# MSP430F249.net
KiCad netlist of a schematic drawn in Altium Designer
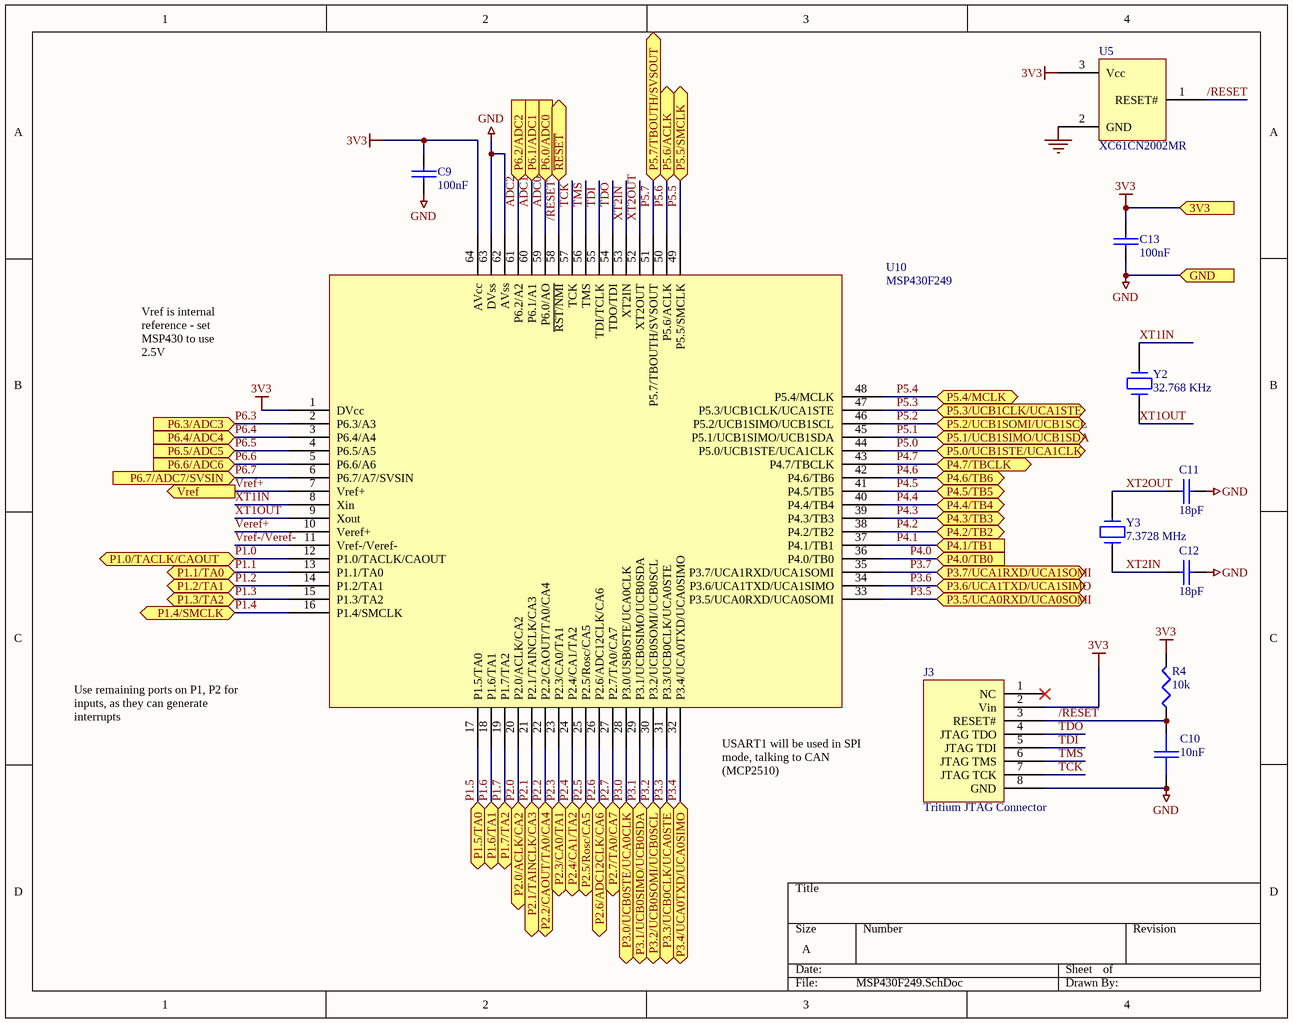
[diagram p0: MSP430F249.SchDoc]

(export (version "E")
  (design (tool "Eeschema 10.0.6"))
  (components
    (comp (ref "C9")
      (value "100nF")
      (footprint "0603")
      (description "Capacitor")
      (libsource (lib "*") (part "CAP"))
    )
    (comp (ref "C10")
      (value "10nF")
      (footprint "0603")
      (description "Capacitor")
      (libsource (lib "SunswiftLib20030312RR") (part "CAP"))
    )
    (comp (ref "C11")
      (value "18pF")
      (footprint "0603")
      (description "Capacitor")
      (libsource (lib "*") (part "CAP"))
    )
    (comp (ref "C12")
      (value "18pF")
      (footprint "0603")
      (description "Capacitor")
      (libsource (lib "*") (part "CAP"))
    )
    (comp (ref "C13")
      (value "100nF")
      (footprint "0603")
      (description "Capacitor")
      (libsource (lib "*") (part "CAP"))
    )
    (comp (ref "J3")
      (value "Tritium JTAG Connector")
      (footprint "IDC8")
      (description "Tritium JTAG interface for MSP430")
      (libsource (lib "MSP430") (part "430F_JTAG_TRITIUM"))
    )
    (comp (ref "R4")
      (value "10k")
      (footprint "0603")
      (description "Resistor")
      (libsource (lib "SunswiftLib20030312RR") (part "RES1"))
    )
    (comp (ref "U5")
      (value "XC61CN2002MR")
      (footprint "SOT23-3")
      (description "SOT23 reset generator")
      (libsource (lib "*") (part "XC61F"))
    )
    (comp (ref "U10") (value "MSP430F249") (footprint "QFP64") (libsource (lib "MSP430") (part "MSP430F249")))
    (comp (ref "Y2")
      (value "32.768 KHz")
      (footprint "WATCHA")
      (description "Crystal")
      (libsource (lib "*") (part "CRYSTAL"))
    )
    (comp (ref "Y3")
      (value "7.3728 MHz")
      (footprint "HC49/4H")
      (description "Crystal")
      (libsource (lib "*") (part "CRYSTAL"))
    )
  )
  (nets
    (net (code "1") (name "/ADC0") (class "Default")
      (node (ref "U10") (pin "59") (pinfunction "P6.0/AO_59") (pintype "passive"))
    )
    (net (code "2") (name "/ADC1") (class "Default")
      (node (ref "U10") (pin "60") (pinfunction "P6.1/A1_60") (pintype "passive"))
    )
    (net (code "3") (name "/ADC2") (class "Default")
      (node (ref "U10") (pin "61") (pinfunction "P6.2/A2_61") (pintype "passive"))
    )
    (net (code "4") (name "/P1.0") (class "Default")
      (node (ref "U10") (pin "12") (pinfunction "P1.0/TACLK/CAOUT_12") (pintype "passive"))
    )
    (net (code "5") (name "/P1.1") (class "Default")
      (node (ref "U10") (pin "13") (pinfunction "P1.1/TA0_13") (pintype "passive"))
    )
    (net (code "6") (name "/P1.2") (class "Default")
      (node (ref "U10") (pin "14") (pinfunction "P1.2/TA1_14") (pintype "passive"))
    )
    (net (code "7") (name "/P1.3") (class "Default")
      (node (ref "U10") (pin "15") (pinfunction "P1.3/TA2_15") (pintype "passive"))
    )
    (net (code "8") (name "/P1.4") (class "Default")
      (node (ref "U10") (pin "16") (pinfunction "P1.4/SMCLK_16") (pintype "passive"))
    )
    (net (code "9") (name "/P1.5") (class "Default")
      (node (ref "U10") (pin "17") (pinfunction "P1.5/TA0_17") (pintype "passive"))
    )
    (net (code "10") (name "/P1.6") (class "Default")
      (node (ref "U10") (pin "18") (pinfunction "P1.6/TA1_18") (pintype "passive"))
    )
    (net (code "11") (name "/P1.7") (class "Default")
      (node (ref "U10") (pin "19") (pinfunction "P1.7/TA2_19") (pintype "passive"))
    )
    (net (code "12") (name "/P2.0") (class "Default")
      (node (ref "U10") (pin "20") (pinfunction "P2.0/ACLK/CA2_20") (pintype "passive"))
    )
    (net (code "13") (name "/P2.1") (class "Default")
      (node (ref "U10") (pin "21") (pinfunction "P2.1/TAINCLK/CA3_21") (pintype "passive"))
    )
    (net (code "14") (name "/P2.2") (class "Default")
      (node (ref "U10") (pin "22") (pinfunction "P2.2/CAOUT/TA0/CA4_22") (pintype "passive"))
    )
    (net (code "15") (name "/P2.3") (class "Default")
      (node (ref "U10") (pin "23") (pinfunction "P2.3/CA0/TA1_23") (pintype "passive"))
    )
    (net (code "16") (name "/P2.4") (class "Default")
      (node (ref "U10") (pin "24") (pinfunction "P2.4/CA1/TA2_24") (pintype "passive"))
    )
    (net (code "17") (name "/P2.5") (class "Default")
      (node (ref "U10") (pin "25") (pinfunction "P2.5/Rosc/CA5_25") (pintype "passive"))
    )
    (net (code "18") (name "/P2.6") (class "Default")
      (node (ref "U10") (pin "26") (pinfunction "P2.6/ADC12CLK/CA6_26") (pintype "passive"))
    )
    (net (code "19") (name "/P2.7") (class "Default")
      (node (ref "U10") (pin "27") (pinfunction "P2.7/TA0/CA7_27") (pintype "passive"))
    )
    (net (code "20") (name "/P3.0") (class "Default")
      (node (ref "U10") (pin "28") (pinfunction "P3.0/USB0STE/UCA0CLK_28") (pintype "passive"))
    )
    (net (code "21") (name "/P3.1") (class "Default")
      (node (ref "U10") (pin "29") (pinfunction "P3.1/UCB0SIMO/UCB0SDA_29") (pintype "passive"))
    )
    (net (code "22") (name "/P3.2") (class "Default")
      (node (ref "U10") (pin "30") (pinfunction "P3.2/UCB0SOMI/UCB0SCL_30") (pintype "passive"))
    )
    (net (code "23") (name "/P3.3") (class "Default")
      (node (ref "U10") (pin "31") (pinfunction "P3.3/UCB0CLK/UCA0STE_31") (pintype "passive"))
    )
    (net (code "24") (name "/P3.4") (class "Default")
      (node (ref "U10") (pin "32") (pinfunction "P3.4/UCA0TXD/UCA0SIMO_32") (pintype "passive"))
    )
    (net (code "25") (name "/P3.5") (class "Default")
      (node (ref "U10") (pin "33") (pinfunction "P3.5/UCA0RXD/UCA0SOMI_33") (pintype "passive"))
    )
    (net (code "26") (name "/P3.6") (class "Default")
      (node (ref "U10") (pin "34") (pinfunction "P3.6/UCA1TXD/UCA1SIMO_34") (pintype "passive"))
    )
    (net (code "27") (name "/P3.7") (class "Default")
      (node (ref "U10") (pin "35") (pinfunction "P3.7/UCA1RXD/UCA1SOMI_35") (pintype "passive"))
    )
    (net (code "28") (name "/P4.0") (class "Default")
      (node (ref "U10") (pin "36") (pinfunction "P4.0/TB0_36") (pintype "passive"))
    )
    (net (code "29") (name "/P4.1") (class "Default")
      (node (ref "U10") (pin "37") (pinfunction "P4.1/TB1_37") (pintype "passive"))
    )
    (net (code "30") (name "/P4.2") (class "Default")
      (node (ref "U10") (pin "38") (pinfunction "P4.2/TB2_38") (pintype "passive"))
    )
    (net (code "31") (name "/P4.3") (class "Default")
      (node (ref "U10") (pin "39") (pinfunction "P4.3/TB3_39") (pintype "passive"))
    )
    (net (code "32") (name "/P4.4") (class "Default")
      (node (ref "U10") (pin "40") (pinfunction "P4.4/TB4_40") (pintype "passive"))
    )
    (net (code "33") (name "/P4.5") (class "Default")
      (node (ref "U10") (pin "41") (pinfunction "P4.5/TB5_41") (pintype "passive"))
    )
    (net (code "34") (name "/P4.6") (class "Default")
      (node (ref "U10") (pin "42") (pinfunction "P4.6/TB6_42") (pintype "passive"))
    )
    (net (code "35") (name "/P4.7") (class "Default")
      (node (ref "U10") (pin "43") (pinfunction "P4.7/TBCLK_43") (pintype "passive"))
    )
    (net (code "36") (name "/P5.0") (class "Default")
      (node (ref "U10") (pin "44") (pinfunction "P5.0/UCB1STE/UCA1CLK_44") (pintype "passive"))
    )
    (net (code "37") (name "/P5.1") (class "Default")
      (node (ref "U10") (pin "45") (pinfunction "P5.1/UCB1SIMO/UCB1SDA_45") (pintype "passive"))
    )
    (net (code "38") (name "/P5.2") (class "Default")
      (node (ref "U10") (pin "46") (pinfunction "P5.2/UCB1SIMO/UCB1SCL_46") (pintype "passive"))
    )
    (net (code "39") (name "/P5.3") (class "Default")
      (node (ref "U10") (pin "47") (pinfunction "P5.3/UCB1CLK/UCA1STE_47") (pintype "passive"))
    )
    (net (code "40") (name "/P5.4") (class "Default")
      (node (ref "U10") (pin "48") (pinfunction "P5.4/MCLK_48") (pintype "passive"))
    )
    (net (code "41") (name "/P5.5") (class "Default")
      (node (ref "U10") (pin "49") (pinfunction "P5.5/SMCLK_49") (pintype "passive"))
    )
    (net (code "42") (name "/P5.6") (class "Default")
      (node (ref "U10") (pin "50") (pinfunction "P5.6/ACLK_50") (pintype "passive"))
    )
    (net (code "43") (name "/P5.7") (class "Default")
      (node (ref "U10") (pin "51") (pinfunction "P5.7/TBOUTH/SVSOUT_51") (pintype "passive"))
    )
    (net (code "44") (name "/P6.3") (class "Default")
      (node (ref "U10") (pin "2") (pinfunction "P6.3/A3_2") (pintype "passive"))
    )
    (net (code "45") (name "/P6.4") (class "Default")
      (node (ref "U10") (pin "3") (pinfunction "P6.4/A4_3") (pintype "passive"))
    )
    (net (code "46") (name "/P6.5") (class "Default")
      (node (ref "U10") (pin "4") (pinfunction "P6.5/A5_4") (pintype "passive"))
    )
    (net (code "47") (name "/P6.6") (class "Default")
      (node (ref "U10") (pin "5") (pinfunction "P6.6/A6_5") (pintype "passive"))
    )
    (net (code "48") (name "/P6.7") (class "Default")
      (node (ref "U10") (pin "6") (pinfunction "P6.7/A7/SVSIN_6") (pintype "passive"))
    )
    (net (code "49") (name "/TCK") (class "Default")
      (node (ref "J3") (pin "7") (pinfunction "JTAG_TCK_7") (pintype "passive"))
      (node (ref "U10") (pin "57") (pinfunction "TCK_57") (pintype "passive"))
    )
    (net (code "50") (name "/TDI") (class "Default")
      (node (ref "J3") (pin "5") (pinfunction "JTAG_TDI_5") (pintype "passive"))
      (node (ref "U10") (pin "55") (pinfunction "TDI/TCLK_55") (pintype "passive"))
    )
    (net (code "51") (name "/TDO") (class "Default")
      (node (ref "J3") (pin "4") (pinfunction "JTAG_TDO_4") (pintype "passive"))
      (node (ref "U10") (pin "54") (pinfunction "TDO/TDI_54") (pintype "passive"))
    )
    (net (code "52") (name "/TMS") (class "Default")
      (node (ref "J3") (pin "6") (pinfunction "JTAG_TMS_6") (pintype "passive"))
      (node (ref "U10") (pin "56") (pinfunction "TMS_56") (pintype "passive"))
    )
    (net (code "53") (name "/Veref+") (class "Default")
      (node (ref "U10") (pin "10") (pinfunction "Veref+_10") (pintype "passive"))
    )
    (net (code "54") (name "/Vref+") (class "Default")
      (node (ref "U10") (pin "7") (pinfunction "Vref+_7") (pintype "passive"))
    )
    (net (code "55") (name "/Vref-{slash}Veref-") (class "Default")
      (node (ref "U10") (pin "11") (pinfunction "Vref-/Veref-_11") (pintype "passive"))
    )
    (net (code "56") (name "/XT1IN") (class "Default")
      (node (ref "U10") (pin "8") (pinfunction "Xin_8") (pintype "passive"))
      (node (ref "Y2") (pin "2") (pinfunction "2_2") (pintype "passive"))
    )
    (net (code "57") (name "/XT1OUT") (class "Default")
      (node (ref "U10") (pin "9") (pinfunction "Xout_9") (pintype "passive"))
      (node (ref "Y2") (pin "1") (pinfunction "1_1") (pintype "passive"))
    )
    (net (code "58") (name "/XT2IN") (class "Default")
      (node (ref "C12") (pin "1") (pinfunction "1_1") (pintype "passive"))
      (node (ref "U10") (pin "53") (pinfunction "XT2IN_53") (pintype "passive"))
      (node (ref "Y3") (pin "1") (pinfunction "1_1") (pintype "passive"))
    )
    (net (code "59") (name "/XT2OUT") (class "Default")
      (node (ref "C11") (pin "1") (pinfunction "1_1") (pintype "passive"))
      (node (ref "U10") (pin "52") (pinfunction "XT2OUT_52") (pintype "passive"))
      (node (ref "Y3") (pin "2") (pinfunction "2_2") (pintype "passive"))
    )
    (net (code "60") (name "/{slash}RESET") (class "Default")
      (node (ref "C10") (pin "1") (pinfunction "1_1") (pintype "passive"))
      (node (ref "J3") (pin "3") (pinfunction "RESET#_3") (pintype "passive"))
      (node (ref "R4") (pin "1") (pinfunction "1_1") (pintype "passive"))
      (node (ref "U10") (pin "58") (pinfunction "RST/NMI_58") (pintype "passive"))
      (node (ref "U5") (pin "1") (pinfunction "RESET#_1") (pintype "passive"))
    )
    (net (code "61") (name "3V3") (class "Default")
      (node (ref "C13") (pin "1") (pinfunction "1_1") (pintype "passive"))
      (node (ref "C9") (pin "1") (pinfunction "1_1") (pintype "passive"))
      (node (ref "J3") (pin "2") (pinfunction "Vin_2") (pintype "passive"))
      (node (ref "R4") (pin "2") (pinfunction "2_2") (pintype "passive"))
      (node (ref "U10") (pin "1") (pinfunction "DVcc_1") (pintype "passive"))
      (node (ref "U10") (pin "64") (pinfunction "AVcc_64") (pintype "passive"))
      (node (ref "U5") (pin "3") (pinfunction "Vcc_3") (pintype "passive"))
    )
    (net (code "62") (name "GND") (class "Default")
      (node (ref "C10") (pin "2") (pinfunction "2_2") (pintype "passive"))
      (node (ref "C11") (pin "2") (pinfunction "2_2") (pintype "passive"))
      (node (ref "C12") (pin "2") (pinfunction "2_2") (pintype "passive"))
      (node (ref "C13") (pin "2") (pinfunction "2_2") (pintype "passive"))
      (node (ref "C9") (pin "2") (pinfunction "2_2") (pintype "passive"))
      (node (ref "J3") (pin "8") (pinfunction "GND_8") (pintype "passive"))
      (node (ref "U10") (pin "62") (pinfunction "AVss_62") (pintype "passive"))
      (node (ref "U10") (pin "63") (pinfunction "DVss_63") (pintype "passive"))
      (node (ref "U5") (pin "2") (pinfunction "GND_2") (pintype "passive"))
    )
    (net (code "63") (name "unconnected-(J3-NC-Pad1)") (class "Default")
      (node (ref "J3") (pin "1") (pinfunction "NC_1") (pintype "passive+no_connect"))
    )
  )
)
